# CLK_Distribution.net
KiCad netlist of a schematic drawn in Altium Designer
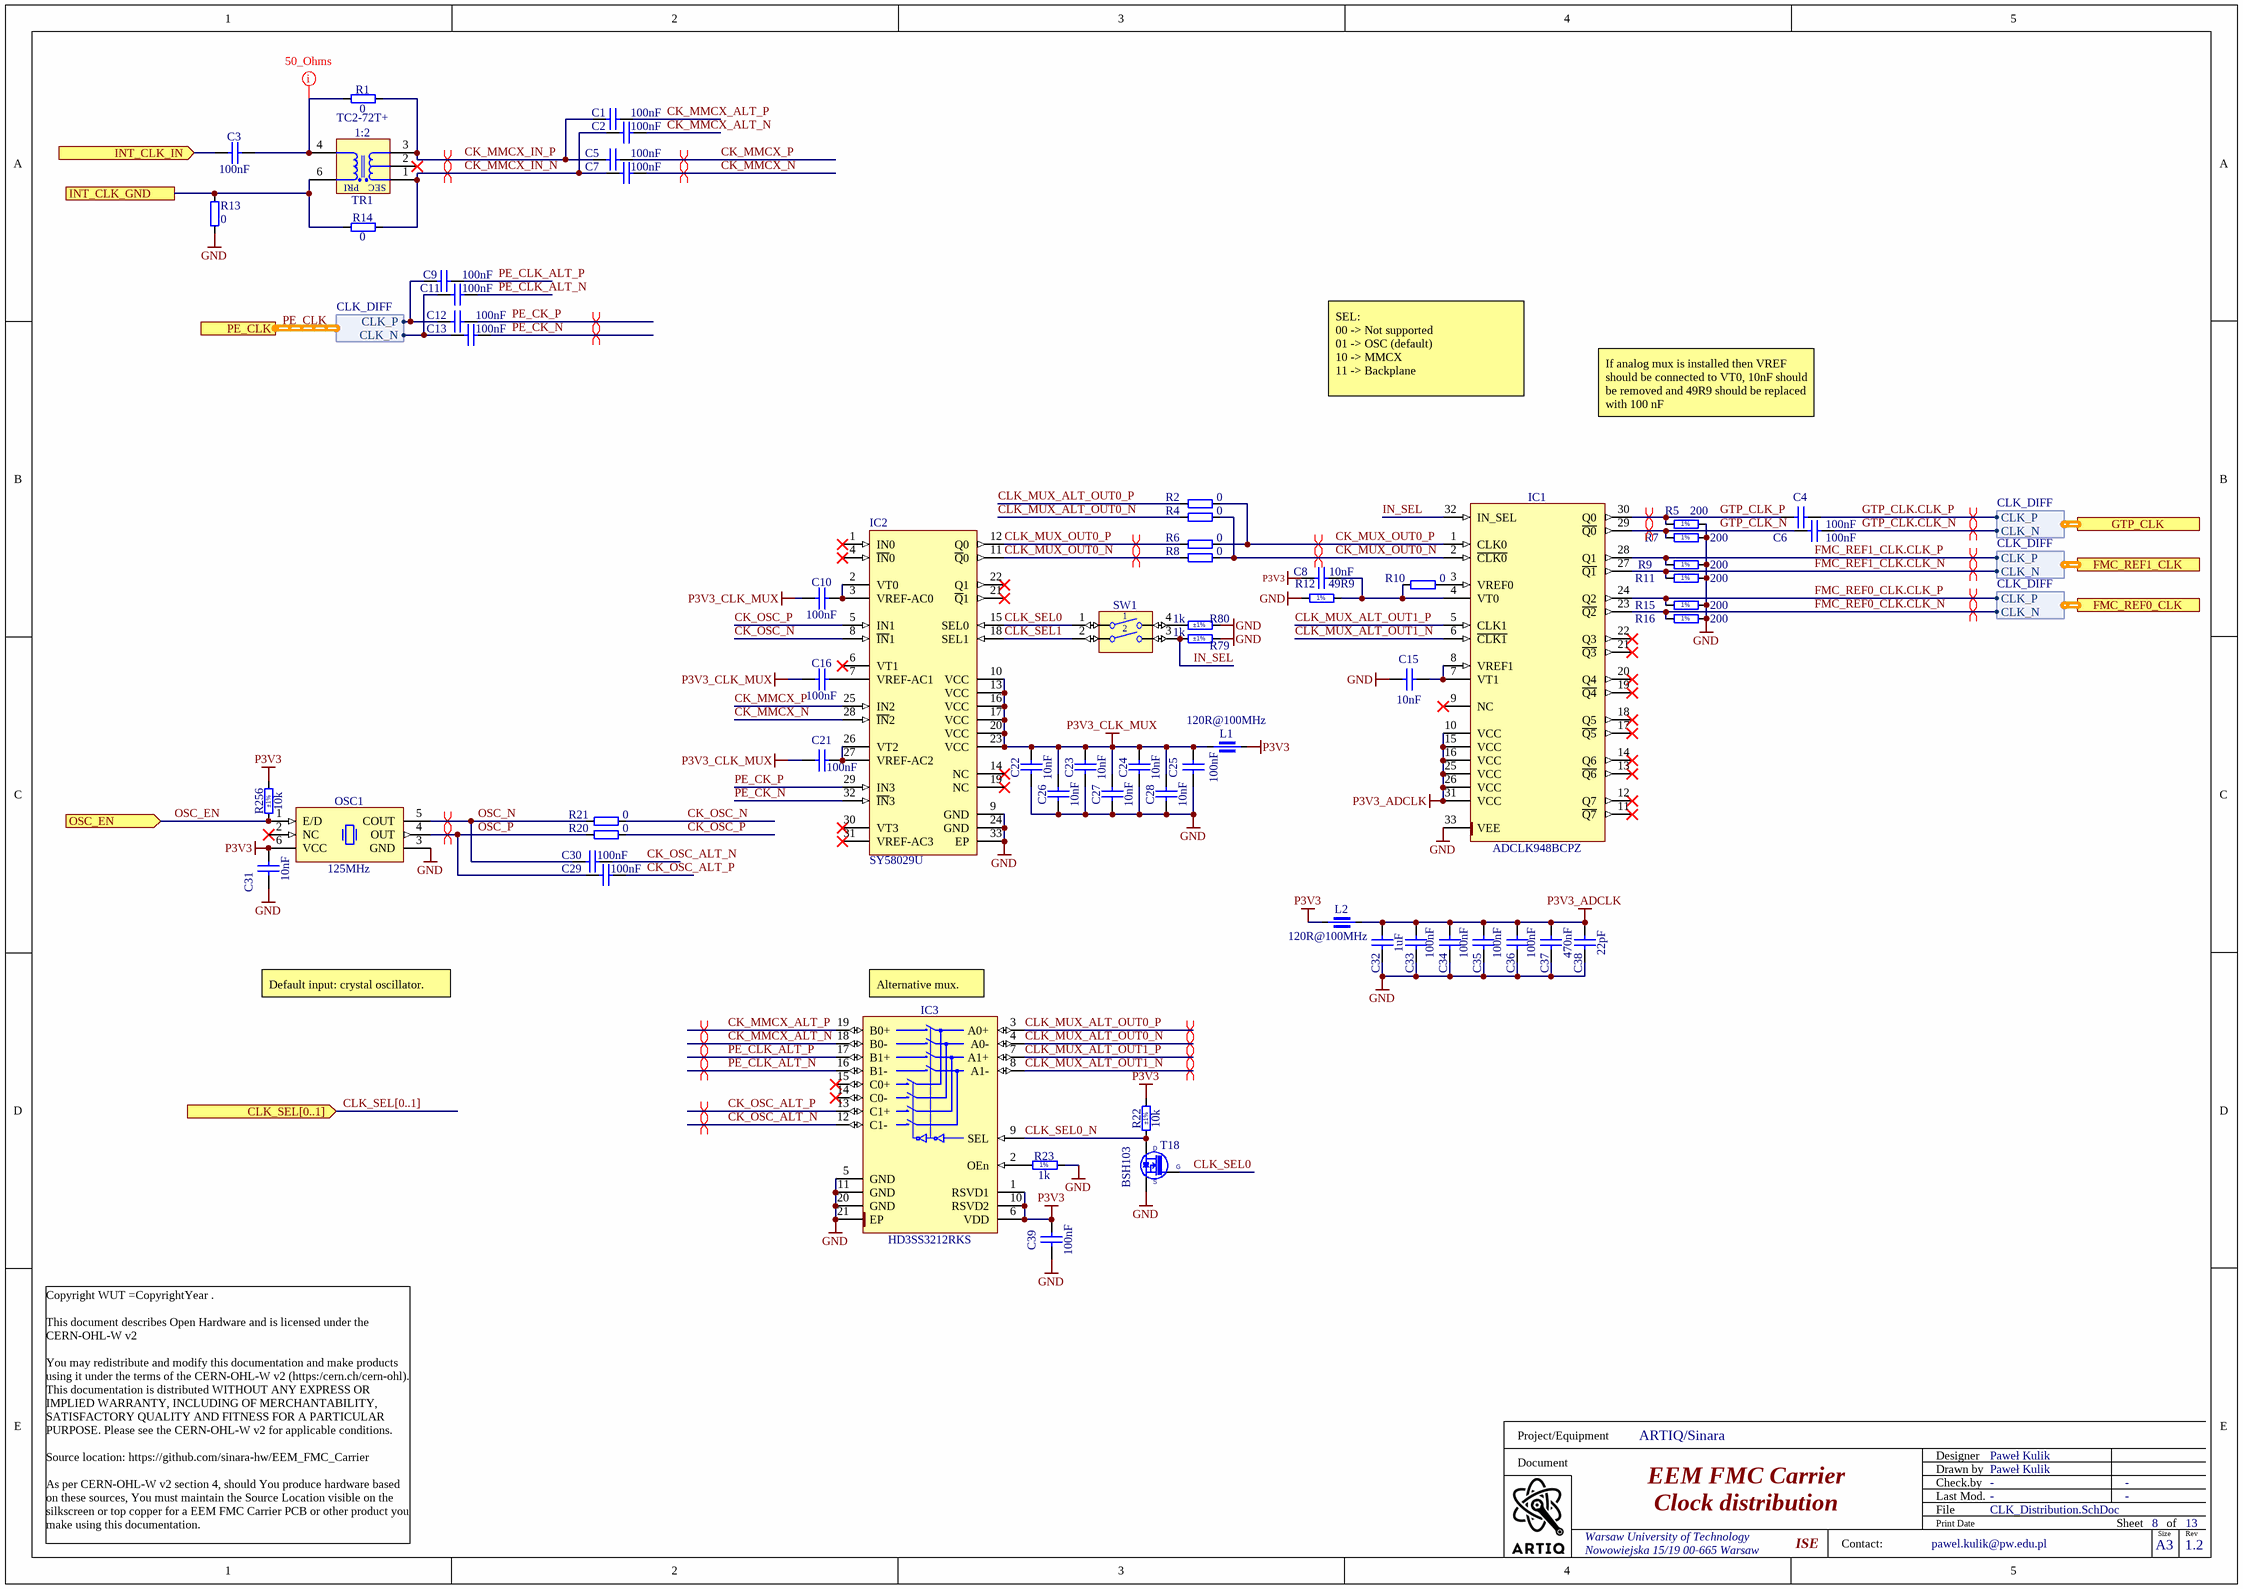
[diagram p0: CLK_Distribution.SchDoc]

(export (version "E")
  (design (tool "Eeschema 10.0.6"))
  (components
    (comp (ref "C1")
      (value "100nF")
      (footprint "CAPC1005X55N")
      (description "Non-polarised capacitor")
      (fields
        (field (name "PART NUMBER") "CC0402_100NF_16V_10%_X5R")
        (field (name "VOLTAGE") "16V")
        (field (name "AUTHOR") "CERN DEM JLC")
      )
      (libsource (lib "Capacitors") (part "Capacitor - non polarized"))
    )
    (comp (ref "C2")
      (value "100nF")
      (footprint "CAPC1005X55N")
      (description "Non-polarised capacitor")
      (fields
        (field (name "PART NUMBER") "CC0402_100NF_16V_10%_X5R")
        (field (name "VOLTAGE") "16V")
        (field (name "AUTHOR") "CERN DEM JLC")
      )
      (libsource (lib "Capacitors") (part "Capacitor - non polarized"))
    )
    (comp (ref "C3")
      (value "100nF")
      (footprint "CAPC1005X55N")
      (description "Non-polarised capacitor")
      (fields
        (field (name "PART NUMBER") "CC0402_100NF_16V_10%_X5R")
        (field (name "VOLTAGE") "16V")
        (field (name "AUTHOR") "CERN DEM JLC")
      )
      (libsource (lib "Capacitors") (part "Capacitor - non polarized"))
    )
    (comp (ref "C4")
      (value "100nF")
      (footprint "CAPC1005X55N")
      (description "Non-polarised capacitor")
      (fields
        (field (name "PART NUMBER") "CC0402_100NF_16V_10%_X5R")
        (field (name "VOLTAGE") "16V")
        (field (name "AUTHOR") "CERN DEM JLC")
      )
      (libsource (lib "Capacitors") (part "Capacitor - non polarized"))
    )
    (comp (ref "C5")
      (value "100nF")
      (footprint "CAPC1005X55N")
      (description "Non-polarised capacitor")
      (fields
        (field (name "PART NUMBER") "CC0402_100NF_16V_10%_X5R")
        (field (name "VOLTAGE") "16V")
        (field (name "AUTHOR") "CERN DEM JLC")
      )
      (libsource (lib "Capacitors") (part "Capacitor - non polarized"))
    )
    (comp (ref "C6")
      (value "100nF")
      (footprint "CAPC1005X55N")
      (description "Non-polarised capacitor")
      (fields
        (field (name "PART NUMBER") "CC0402_100NF_16V_10%_X5R")
        (field (name "VOLTAGE") "16V")
        (field (name "AUTHOR") "CERN DEM JLC")
      )
      (libsource (lib "Capacitors") (part "Capacitor - non polarized"))
    )
    (comp (ref "C7")
      (value "100nF")
      (footprint "CAPC1005X55N")
      (description "Non-polarised capacitor")
      (fields
        (field (name "PART NUMBER") "CC0402_100NF_16V_10%_X5R")
        (field (name "VOLTAGE") "16V")
        (field (name "AUTHOR") "CERN DEM JLC")
      )
      (libsource (lib "Capacitors") (part "Capacitor - non polarized"))
    )
    (comp (ref "C8")
      (value "10nF")
      (footprint "CAPC1005X55N")
      (description "Non-polarised capacitor")
      (fields
        (field (name "PART NUMBER") "CC0402_10NF_16V_10%_X7R")
        (field (name "VOLTAGE") "16V")
        (field (name "AUTHOR") "CERN DEM JLC")
      )
      (libsource (lib "Capacitors") (part "Capacitor - non polarized"))
    )
    (comp (ref "C9")
      (value "100nF")
      (footprint "CAPC1005X55N")
      (description "Non-polarised capacitor")
      (fields
        (field (name "PART NUMBER") "CC0402_100NF_16V_10%_X5R")
        (field (name "VOLTAGE") "16V")
        (field (name "AUTHOR") "CERN DEM JLC")
      )
      (libsource (lib "Capacitors") (part "Capacitor - non polarized"))
    )
    (comp (ref "C10")
      (value "100nF")
      (footprint "CAPC1005X55N")
      (description "Non-polarised capacitor")
      (fields
        (field (name "PART NUMBER") "CC0402_100NF_16V_10%_X5R")
        (field (name "VOLTAGE") "16V")
        (field (name "AUTHOR") "CERN DEM JLC")
      )
      (libsource (lib "Capacitors") (part "Capacitor - non polarized"))
    )
    (comp (ref "C11")
      (value "100nF")
      (footprint "CAPC1005X55N")
      (description "Non-polarised capacitor")
      (fields
        (field (name "PART NUMBER") "CC0402_100NF_16V_10%_X5R")
        (field (name "VOLTAGE") "16V")
        (field (name "AUTHOR") "CERN DEM JLC")
      )
      (libsource (lib "Capacitors") (part "Capacitor - non polarized"))
    )
    (comp (ref "C12")
      (value "100nF")
      (footprint "CAPC1005X55N")
      (description "Non-polarised capacitor")
      (fields
        (field (name "PART NUMBER") "CC0402_100NF_16V_10%_X5R")
        (field (name "VOLTAGE") "16V")
        (field (name "AUTHOR") "CERN DEM JLC")
      )
      (libsource (lib "Capacitors") (part "Capacitor - non polarized"))
    )
    (comp (ref "C13")
      (value "100nF")
      (footprint "CAPC1005X55N")
      (description "Non-polarised capacitor")
      (fields
        (field (name "PART NUMBER") "CC0402_100NF_16V_10%_X5R")
        (field (name "VOLTAGE") "16V")
        (field (name "AUTHOR") "CERN DEM JLC")
      )
      (libsource (lib "Capacitors") (part "Capacitor - non polarized"))
    )
    (comp (ref "C15")
      (value "10nF")
      (footprint "CAPC1005X55N")
      (description "Non-polarised capacitor")
      (fields
        (field (name "PART NUMBER") "CC0402_10NF_16V_10%_X7R")
        (field (name "VOLTAGE") "16V")
        (field (name "AUTHOR") "CERN DEM JLC")
      )
      (libsource (lib "Capacitors") (part "Capacitor - non polarized"))
    )
    (comp (ref "C16")
      (value "100nF")
      (footprint "CAPC1005X55N")
      (description "Non-polarised capacitor")
      (fields
        (field (name "PART NUMBER") "CC0402_100NF_16V_10%_X5R")
        (field (name "VOLTAGE") "16V")
        (field (name "AUTHOR") "CERN DEM JLC")
      )
      (libsource (lib "Capacitors") (part "Capacitor - non polarized"))
    )
    (comp (ref "C21")
      (value "100nF")
      (footprint "CAPC1005X55N")
      (description "Non-polarised capacitor")
      (fields
        (field (name "PART NUMBER") "CC0402_100NF_16V_10%_X5R")
        (field (name "VOLTAGE") "16V")
        (field (name "AUTHOR") "CERN DEM JLC")
      )
      (libsource (lib "Capacitors") (part "Capacitor - non polarized"))
    )
    (comp (ref "C22")
      (value "10nF")
      (footprint "CAPC1005X55N")
      (description "Non-polarised capacitor")
      (fields
        (field (name "PART NUMBER") "CC0402_10NF_16V_10%_X7R")
        (field (name "VOLTAGE") "16V")
        (field (name "AUTHOR") "CERN DEM JLC")
      )
      (libsource (lib "Capacitors") (part "Capacitor - non polarized"))
    )
    (comp (ref "C23")
      (value "10nF")
      (footprint "CAPC1005X55N")
      (description "Non-polarised capacitor")
      (fields
        (field (name "PART NUMBER") "CC0402_10NF_16V_10%_X7R")
        (field (name "VOLTAGE") "16V")
        (field (name "AUTHOR") "CERN DEM JLC")
      )
      (libsource (lib "Capacitors") (part "Capacitor - non polarized"))
    )
    (comp (ref "C24")
      (value "10nF")
      (footprint "CAPC1005X55N")
      (description "Non-polarised capacitor")
      (fields
        (field (name "PART NUMBER") "CC0402_10NF_16V_10%_X7R")
        (field (name "VOLTAGE") "16V")
        (field (name "AUTHOR") "CERN DEM JLC")
      )
      (libsource (lib "Capacitors") (part "Capacitor - non polarized"))
    )
    (comp (ref "C25")
      (value "100nF")
      (footprint "CAPC1005X55N")
      (description "Non-polarised capacitor")
      (fields
        (field (name "PART NUMBER") "CC0402_100NF_16V_10%_X5R")
        (field (name "VOLTAGE") "16V")
        (field (name "AUTHOR") "CERN DEM JLC")
      )
      (libsource (lib "Capacitors") (part "Capacitor - non polarized"))
    )
    (comp (ref "C26")
      (value "10nF")
      (footprint "CAPC1005X55N")
      (description "Non-polarised capacitor")
      (fields
        (field (name "PART NUMBER") "CC0402_10NF_16V_10%_X7R")
        (field (name "VOLTAGE") "16V")
        (field (name "AUTHOR") "CERN DEM JLC")
      )
      (libsource (lib "Capacitors") (part "Capacitor - non polarized"))
    )
    (comp (ref "C27")
      (value "10nF")
      (footprint "CAPC1005X55N")
      (description "Non-polarised capacitor")
      (fields
        (field (name "PART NUMBER") "CC0402_10NF_16V_10%_X7R")
        (field (name "VOLTAGE") "16V")
        (field (name "AUTHOR") "CERN DEM JLC")
      )
      (libsource (lib "Capacitors") (part "Capacitor - non polarized"))
    )
    (comp (ref "C28")
      (value "10nF")
      (footprint "CAPC1005X55N")
      (description "Non-polarised capacitor")
      (fields
        (field (name "PART NUMBER") "CC0402_10NF_16V_10%_X7R")
        (field (name "VOLTAGE") "16V")
        (field (name "AUTHOR") "CERN DEM JLC")
      )
      (libsource (lib "Capacitors") (part "Capacitor - non polarized"))
    )
    (comp (ref "C29")
      (value "100nF")
      (footprint "CAPC1005X55N")
      (description "Non-polarised capacitor")
      (fields
        (field (name "PART NUMBER") "CC0402_100NF_16V_10%_X5R")
        (field (name "VOLTAGE") "16V")
        (field (name "AUTHOR") "CERN DEM JLC")
      )
      (libsource (lib "Capacitors") (part "Capacitor - non polarized"))
    )
    (comp (ref "C30")
      (value "100nF")
      (footprint "CAPC1005X55N")
      (description "Non-polarised capacitor")
      (fields
        (field (name "PART NUMBER") "CC0402_100NF_16V_10%_X5R")
        (field (name "VOLTAGE") "16V")
        (field (name "AUTHOR") "CERN DEM JLC")
      )
      (libsource (lib "Capacitors") (part "Capacitor - non polarized"))
    )
    (comp (ref "C31")
      (value "10nF")
      (footprint "CAPC1005X55N")
      (description "Non-polarised capacitor")
      (fields
        (field (name "PART NUMBER") "CC0402_10NF_16V_10%_X7R")
        (field (name "VOLTAGE") "16V")
        (field (name "AUTHOR") "CERN DEM JLC")
      )
      (libsource (lib "Capacitors") (part "Capacitor - non polarized"))
    )
    (comp (ref "C32")
      (value "1uF")
      (footprint "CAPC1005X55N")
      (description "Non-polarised capacitor")
      (fields
        (field (name "PART NUMBER") "CC0402_1UF_16V_10%_X5R")
        (field (name "VOLTAGE") "16V")
        (field (name "AUTHOR") "CERN DEM JLC")
      )
      (libsource (lib "Capacitors") (part "Capacitor - non polarized"))
    )
    (comp (ref "C33")
      (value "100nF")
      (footprint "CAPC0603X33N")
      (description "Non-polarised capacitor")
      (fields
        (field (name "PART NUMBER") "CC0201_100NF_6.3V_10%_X5R")
        (field (name "VOLTAGE") "6.3V")
        (field (name "AUTHOR") "CERN DEM JLC")
      )
      (libsource (lib "Capacitors") (part "Capacitor - non polarized"))
    )
    (comp (ref "C34")
      (value "100nF")
      (footprint "CAPC0603X33N")
      (description "Non-polarised capacitor")
      (fields
        (field (name "PART NUMBER") "CC0201_100NF_6.3V_10%_X5R")
        (field (name "VOLTAGE") "6.3V")
        (field (name "AUTHOR") "CERN DEM JLC")
      )
      (libsource (lib "Capacitors") (part "Capacitor - non polarized"))
    )
    (comp (ref "C35")
      (value "100nF")
      (footprint "CAPC0603X33N")
      (description "Non-polarised capacitor")
      (fields
        (field (name "PART NUMBER") "CC0201_100NF_6.3V_10%_X5R")
        (field (name "VOLTAGE") "6.3V")
        (field (name "AUTHOR") "CERN DEM JLC")
      )
      (libsource (lib "Capacitors") (part "Capacitor - non polarized"))
    )
    (comp (ref "C36")
      (value "100nF")
      (footprint "CAPC0603X33N")
      (description "Non-polarised capacitor")
      (fields
        (field (name "PART NUMBER") "CC0201_100NF_6.3V_10%_X5R")
        (field (name "VOLTAGE") "6.3V")
        (field (name "AUTHOR") "CERN DEM JLC")
      )
      (libsource (lib "Capacitors") (part "Capacitor - non polarized"))
    )
    (comp (ref "C37")
      (value "470nF")
      (footprint "CAPC0603X33N")
      (description "Non-polarised capacitor")
      (fields
        (field (name "PART NUMBER") "CC0201_470NF_4V_20%_X5R")
        (field (name "VOLTAGE") "4V")
        (field (name "AUTHOR") "CERN DEM JLC")
      )
      (libsource (lib "Capacitors") (part "Capacitor - non polarized"))
    )
    (comp (ref "C38")
      (value "22pF")
      (footprint "CAPC1005X55N")
      (description "Non-polarised capacitor")
      (fields
        (field (name "PART NUMBER") "CC0402_22PF_50V_5%_C0G")
        (field (name "VOLTAGE") "50V")
        (field (name "AUTHOR") "CERN DEM JLC")
      )
      (libsource (lib "Capacitors") (part "Capacitor - non polarized"))
    )
    (comp (ref "C39")
      (value "100nF")
      (footprint "CAPC1005X55N")
      (description "Non-polarised capacitor")
      (fields
        (field (name "PART NUMBER") "CC0402_100NF_25V_10%_X7R_YUDEN_TMK105B7104KVHF")
        (field (name "VOLTAGE") "25V")
        (field (name "AUTHOR") "CERN DEM JLC")
      )
      (libsource (lib "Capacitors") (part "Capacitor - non polarized"))
    )
    (comp (ref "IC1")
      (value "ADCLK948BCPZ")
      (footprint "QFN50P500X500X80-33N-S285")
      (description "Two Selectable Inputs, 8 LVPECL Outputs, SiGe Clock Fanout Buffer")
      (fields (field (name "MANUFACTURER") "ANALOG DEVICES") (field (name "AUTHOR") "CERN DEM MR"))
      (libsource (lib "ICs And Semiconductors") (part "ADCLK948"))
    )
    (comp (ref "IC2")
      (value "SY58029U")
      (footprint "MLF-32")
      (description "ULTRA PRECISION DIFFERENTIAL LVPECL 4:1 MUX with 1:2 FANOUT and INTERNAL TERMINATION")
      (fields (field (name "MANUFACTURER") "Microchip"))
      (libsource (lib "Schlib1") (part "SY58029U"))
    )
    (comp (ref "IC3")
      (value "HD3SS3212RKS")
      (footprint "TEXAS_RKS0020A")
      (description "Two-Channel Differential 2:1/1:2 USB3.1 Mux/Demux")
      (fields (field (name "MANUFACTURER") "TEXAS INSTRUMENTS") (field (name "AUTHOR") "CERN DEM BC"))
      (libsource (lib "ICs And Semiconductors") (part "HD3SS3212RKS"))
    )
    (comp (ref "L1")
      (value "120R@100MHz")
      (footprint "INDC1608X65N")
      (fields
        (field (name "PART NUMBER") "IND0603_MURATA_BLM18SG121TN1D")
        (field (name "POWER") "3A")
        (field (name "MANUFACTURER") "MURATA")
        (field (name "AUTHOR") "CERN DEM JLC")
      )
      (libsource (lib "Inductors & Transformers") (part "Ferrite Bead"))
    )
    (comp (ref "L2")
      (value "120R@100MHz")
      (footprint "INDC1608X65N")
      (fields
        (field (name "PART NUMBER") "IND0603_MURATA_BLM18SG121TN1D")
        (field (name "POWER") "3A")
        (field (name "MANUFACTURER") "MURATA")
        (field (name "AUTHOR") "CERN DEM JLC")
      )
      (libsource (lib "Inductors & Transformers") (part "Ferrite Bead"))
    )
    (comp (ref "OSC1")
      (value "125MHz")
      (footprint "OSC_CRYSTEK_CCLD-033")
      (description "3.3V, ± 50ppm, 0°C to +70°C, Surface Mount LVDS Clock Oscillator (CCLD-033 Series)")
      (fields
        (field (name "PART NUMBER") "OSC_125MHZ_CRYSTEK_CCLD-033-50-125.000")
        (field (name "MANUFACTURER") "CRYSTEK CRYSTAL")
        (field (name "AUTHOR") "CERN DEM JLC")
      )
      (libsource (lib "Schlib1") (part "OSC_CRYSTEK_CCLD-033"))
    )
    (comp (ref "R1")
      (value "0")
      (footprint "RESC1005X40N")
      (description "Resistor")
      (fields
        (field (name "PART NUMBER") "R0402_0R_JUMPER")
        (field (name "MANUFACTURER") "GENERIC")
        (field (name "AUTHOR") "CERN DEM JLC")
      )
      (libsource (lib "Resistors") (part "Resistor"))
    )
    (comp (ref "R2")
      (value "0")
      (footprint "RESC0603X28N")
      (description "Resistor")
      (fields
        (field (name "PART NUMBER") "R0201_0R_JUMPER")
        (field (name "MANUFACTURER") "GENERIC")
        (field (name "AUTHOR") "CERN DEM JLC")
      )
      (libsource (lib "Resistors") (part "Resistor"))
    )
    (comp (ref "R4")
      (value "0")
      (footprint "RESC0603X28N")
      (description "Resistor")
      (fields
        (field (name "PART NUMBER") "R0201_0R_JUMPER")
        (field (name "MANUFACTURER") "GENERIC")
        (field (name "AUTHOR") "CERN DEM JLC")
      )
      (libsource (lib "Resistors") (part "Resistor"))
    )
    (comp (ref "R5")
      (value "200")
      (footprint "RESC1005X40N")
      (description "Resistor - 1%")
      (fields
        (field (name "PART NUMBER") "R0402_200R_1%_0.0625W_100PPM")
        (field (name "POWER") "0.0625W")
        (field (name "AUTHOR") "CERN DEM JLC")
      )
      (libsource (lib "Resistors") (part "Resistor - 1%"))
    )
    (comp (ref "R6")
      (value "0")
      (footprint "RESC0603X28N")
      (description "Resistor")
      (fields
        (field (name "PART NUMBER") "R0201_0R_JUMPER")
        (field (name "MANUFACTURER") "GENERIC")
        (field (name "AUTHOR") "CERN DEM JLC")
      )
      (libsource (lib "Resistors") (part "Resistor"))
    )
    (comp (ref "R7")
      (value "200")
      (footprint "RESC1005X40N")
      (description "Resistor - 1%")
      (fields
        (field (name "PART NUMBER") "R0402_200R_1%_0.0625W_100PPM")
        (field (name "POWER") "0.0625W")
        (field (name "AUTHOR") "CERN DEM JLC")
      )
      (libsource (lib "Resistors") (part "Resistor - 1%"))
    )
    (comp (ref "R8")
      (value "0")
      (footprint "RESC0603X28N")
      (description "Resistor")
      (fields
        (field (name "PART NUMBER") "R0201_0R_JUMPER")
        (field (name "MANUFACTURER") "GENERIC")
        (field (name "AUTHOR") "CERN DEM JLC")
      )
      (libsource (lib "Resistors") (part "Resistor"))
    )
    (comp (ref "R9")
      (value "200")
      (footprint "RESC1005X40N")
      (description "Resistor - 1%")
      (fields
        (field (name "PART NUMBER") "R0402_200R_1%_0.0625W_100PPM")
        (field (name "POWER") "0.0625W")
        (field (name "AUTHOR") "CERN DEM JLC")
      )
      (libsource (lib "Resistors") (part "Resistor - 1%"))
    )
    (comp (ref "R10")
      (value "0")
      (footprint "RESC0603X28N")
      (description "Resistor")
      (fields
        (field (name "PART NUMBER") "R0201_0R_JUMPER")
        (field (name "MANUFACTURER") "GENERIC")
        (field (name "AUTHOR") "CERN DEM JLC")
      )
      (libsource (lib "Resistors") (part "Resistor"))
    )
    (comp (ref "R11")
      (value "200")
      (footprint "RESC1005X40N")
      (description "Resistor - 1%")
      (fields
        (field (name "PART NUMBER") "R0402_200R_1%_0.0625W_100PPM")
        (field (name "POWER") "0.0625W")
        (field (name "AUTHOR") "CERN DEM JLC")
      )
      (libsource (lib "Resistors") (part "Resistor - 1%"))
    )
    (comp (ref "R12")
      (value "49R9")
      (footprint "RESC1005X40N")
      (description "Resistor - 1%")
      (fields
        (field (name "PART NUMBER") "R0402_49R9_1%_0.0625W_100PPM")
        (field (name "POWER") "0.0625W")
        (field (name "AUTHOR") "CERN DEM JLC")
      )
      (libsource (lib "Resistors") (part "Resistor - 1%"))
    )
    (comp (ref "R13")
      (value "0")
      (footprint "RESC1005X40N")
      (description "Resistor")
      (fields
        (field (name "PART NUMBER") "R0402_0R_JUMPER")
        (field (name "MANUFACTURER") "GENERIC")
        (field (name "AUTHOR") "CERN DEM JLC")
      )
      (libsource (lib "Resistors") (part "Resistor"))
    )
    (comp (ref "R14")
      (value "0")
      (footprint "RESC1005X40N")
      (description "Resistor")
      (fields
        (field (name "PART NUMBER") "R0402_0R_JUMPER")
        (field (name "MANUFACTURER") "GENERIC")
        (field (name "AUTHOR") "CERN DEM JLC")
      )
      (libsource (lib "Resistors") (part "Resistor"))
    )
    (comp (ref "R15")
      (value "200")
      (footprint "RESC1005X40N")
      (description "Resistor - 1%")
      (fields
        (field (name "PART NUMBER") "R0402_200R_1%_0.0625W_100PPM")
        (field (name "POWER") "0.0625W")
        (field (name "AUTHOR") "CERN DEM JLC")
      )
      (libsource (lib "Resistors") (part "Resistor - 1%"))
    )
    (comp (ref "R16")
      (value "200")
      (footprint "RESC1005X40N")
      (description "Resistor - 1%")
      (fields
        (field (name "PART NUMBER") "R0402_200R_1%_0.0625W_100PPM")
        (field (name "POWER") "0.0625W")
        (field (name "AUTHOR") "CERN DEM JLC")
      )
      (libsource (lib "Resistors") (part "Resistor - 1%"))
    )
    (comp (ref "R20")
      (value "0")
      (footprint "RESC1005X40N")
      (description "Resistor")
      (fields
        (field (name "PART NUMBER") "R0402_0R_JUMPER")
        (field (name "MANUFACTURER") "GENERIC")
        (field (name "AUTHOR") "CERN DEM JLC")
      )
      (libsource (lib "Resistors") (part "Resistor"))
    )
    (comp (ref "R21")
      (value "0")
      (footprint "RESC1005X40N")
      (description "Resistor")
      (fields
        (field (name "PART NUMBER") "R0402_0R_JUMPER")
        (field (name "MANUFACTURER") "GENERIC")
        (field (name "AUTHOR") "CERN DEM JLC")
      )
      (libsource (lib "Resistors") (part "Resistor"))
    )
    (comp (ref "R22")
      (value "10k")
      (footprint "RESC1005X40N")
      (description "Resistor - 1%")
      (fields
        (field (name "TOLERANCE") "±1%")
        (field (name "PART NUMBER") "R0402_10K_1%_0.0625W_100PPM")
        (field (name "POWER") "0.0625W")
        (field (name "AUTHOR") "CERN DEM JLC")
      )
      (libsource (lib "Resistors") (part "Resistor - 1%"))
    )
    (comp (ref "R23")
      (value "1k")
      (footprint "RESC1005X40N")
      (description "Resistor - 1%")
      (fields
        (field (name "PART NUMBER") "R0402_1K_1%_0.0625W_100PPM")
        (field (name "POWER") "0.0625W")
        (field (name "AUTHOR") "CERN DEM JLC")
      )
      (libsource (lib "Resistors") (part "Resistor - 1%"))
    )
    (comp (ref "R79")
      (value "1k")
      (footprint "RESC1005X40N")
      (description "Resistor - 1%")
      (fields
        (field (name "TOLERANCE") "±1%")
        (field (name "PART NUMBER") "R0402_1K_1%_0.0625W_100PPM")
        (field (name "POWER") "0.0625W")
        (field (name "AUTHOR") "CERN DEM JLC")
      )
      (libsource (lib "Resistors") (part "Resistor - 1%"))
    )
    (comp (ref "R80")
      (value "1k")
      (footprint "RESC1005X40N")
      (description "Resistor - 1%")
      (fields
        (field (name "TOLERANCE") "±1%")
        (field (name "PART NUMBER") "R0402_1K_1%_0.0625W_100PPM")
        (field (name "POWER") "0.0625W")
        (field (name "AUTHOR") "CERN DEM JLC")
      )
      (libsource (lib "Resistors") (part "Resistor - 1%"))
    )
    (comp (ref "R256")
      (value "10k")
      (footprint "RESC1005X40N")
      (description "Resistor - 1%")
      (fields
        (field (name "TOLERANCE") "±1%")
        (field (name "PART NUMBER") "R0402_10K_1%_0.0625W_100PPM")
        (field (name "POWER") "0.0625W")
        (field (name "AUTHOR") "CERN DEM JLC")
      )
      (libsource (lib "Resistors") (part "Resistor - 1%"))
    )
    (comp (ref "SW1")
      (value "Switch")
      (footprint "SW_TYCO_1571983-1")
      (description "2 Ways SPST DIP Switch")
      (fields
        (field (name "PART NUMBER") "SW_TYCO_1571983-1")
        (field (name "MANUFACTURER") "TYCO")
        (field (name "AUTHOR") "CERN DEM JLC")
      )
      (libsource (lib "Eletro-mechanical") (part "SW 2x SPST DIP Switch"))
    )
    (comp (ref "T18")
      (value "BSH103")
      (footprint "SOT95P230X110-3N")
      (description "N-CHANNEL MOSFET WITH DIODE")
      (fields (field (name "MANUFACTURER") "NEXPERIA") (field (name "AUTHOR") "CERN DEM JLC"))
      (libsource (lib "ICs And Semiconductors") (part "N-MOSFET-D 1G 2S 3D"))
    )
    (comp (ref "TR1")
      (value "1:2")
      (footprint "XFMR_MINI-CIRCUITS_AT1521")
      (description "50 Ohms 10 to 700 MHzz RF Transformer")
      (fields
        (field (name "MANUFACTURER") "MINI-CIRCUITS")
        (field (name "MANUFACTURER PART NUMBER") "TC2-72T+")
        (field (name "PART NUMBER") "XFMR_MINI-CIRCUITS_TC2-72T+")
        (field (name "AUTHOR") "GK")
      )
      (libsource (lib "Inductors_Transformers") (part "XFMR_MINI-CIRCUITS_TC2-72T+"))
    )
  )
  (nets
    (net (code "3") (name "/CK_MMCX_ALT_N") (class "Default")
      (node (ref "C2") (pin "2") (pinfunction "2_2") (pintype "passive"))
      (node (ref "IC3") (pin "18") (pinfunction "B0-_18") (pintype "bidirectional"))
    )
    (net (code "4") (name "/CK_MMCX_ALT_P") (class "Default")
      (node (ref "C1") (pin "2") (pinfunction "2_2") (pintype "passive"))
      (node (ref "IC3") (pin "19") (pinfunction "B0+_19") (pintype "bidirectional"))
    )
    (net (code "5") (name "/CK_MMCX_IN_N") (class "Default")
      (node (ref "C2") (pin "1") (pinfunction "1_1") (pintype "passive"))
      (node (ref "C7") (pin "1") (pinfunction "1_1") (pintype "passive"))
      (node (ref "R14") (pin "2") (pinfunction "2_2") (pintype "passive"))
      (node (ref "TR1") (pin "1") (pinfunction "SDOT_1") (pintype "passive"))
    )
    (net (code "6") (name "/CK_MMCX_IN_P") (class "Default")
      (node (ref "C1") (pin "1") (pinfunction "1_1") (pintype "passive"))
      (node (ref "C5") (pin "1") (pinfunction "1_1") (pintype "passive"))
      (node (ref "R1") (pin "2") (pinfunction "2_2") (pintype "passive"))
      (node (ref "TR1") (pin "3") (pinfunction "S_3") (pintype "passive"))
    )
    (net (code "7") (name "/CK_MMCX_N") (class "Default")
      (node (ref "C7") (pin "2") (pinfunction "2_2") (pintype "passive"))
      (node (ref "IC2") (pin "28") (pinfunction "~{IN}2_28") (pintype "input"))
    )
    (net (code "8") (name "/CK_MMCX_P") (class "Default")
      (node (ref "C5") (pin "2") (pinfunction "2_2") (pintype "passive"))
      (node (ref "IC2") (pin "25") (pinfunction "IN2_25") (pintype "input"))
    )
    (net (code "9") (name "/CK_MUX_OUT0_N") (class "Default")
      (node (ref "IC1") (pin "2") (pinfunction "~{CLK0}_2") (pintype "input"))
      (node (ref "R4") (pin "2") (pinfunction "2_2") (pintype "passive"))
      (node (ref "R8") (pin "2") (pinfunction "2_2") (pintype "passive"))
    )
    (net (code "10") (name "/CK_MUX_OUT0_P") (class "Default")
      (node (ref "IC1") (pin "1") (pinfunction "CLK0_1") (pintype "input"))
      (node (ref "R2") (pin "2") (pinfunction "2_2") (pintype "passive"))
      (node (ref "R6") (pin "2") (pinfunction "2_2") (pintype "passive"))
    )
    (net (code "11") (name "/CK_OSC_ALT_N") (class "Default")
      (node (ref "C30") (pin "2") (pinfunction "2_2") (pintype "passive"))
      (node (ref "IC3") (pin "12") (pinfunction "C1-_12") (pintype "bidirectional"))
    )
    (net (code "12") (name "/CK_OSC_ALT_P") (class "Default")
      (node (ref "C29") (pin "2") (pinfunction "2_2") (pintype "passive"))
      (node (ref "IC3") (pin "13") (pinfunction "C1+_13") (pintype "bidirectional"))
    )
    (net (code "13") (name "/CK_OSC_N") (class "Default")
      (node (ref "IC2") (pin "8") (pinfunction "~{IN}1_8") (pintype "input"))
      (node (ref "R21") (pin "2") (pinfunction "2_2") (pintype "passive"))
    )
    (net (code "14") (name "/CK_OSC_P") (class "Default")
      (node (ref "IC2") (pin "5") (pinfunction "IN1_5") (pintype "input"))
      (node (ref "R20") (pin "2") (pinfunction "2_2") (pintype "passive"))
    )
    (net (code "15") (name "/CLK_MUX_ALT_OUT0_N") (class "Default")
      (node (ref "IC3") (pin "4") (pinfunction "A0-_4") (pintype "bidirectional"))
      (node (ref "R4") (pin "1") (pinfunction "1_1") (pintype "passive"))
    )
    (net (code "16") (name "/CLK_MUX_ALT_OUT0_P") (class "Default")
      (node (ref "IC3") (pin "3") (pinfunction "A0+_3") (pintype "bidirectional"))
      (node (ref "R2") (pin "1") (pinfunction "1_1") (pintype "passive"))
    )
    (net (code "17") (name "/CLK_MUX_ALT_OUT1_N") (class "Default")
      (node (ref "IC1") (pin "6") (pinfunction "~{CLK1}_6") (pintype "input"))
      (node (ref "IC3") (pin "8") (pinfunction "A1-_8") (pintype "bidirectional"))
    )
    (net (code "18") (name "/CLK_MUX_ALT_OUT1_P") (class "Default")
      (node (ref "IC1") (pin "5") (pinfunction "CLK1_5") (pintype "input"))
      (node (ref "IC3") (pin "7") (pinfunction "A1+_7") (pintype "bidirectional"))
    )
    (net (code "19") (name "/CLK_MUX_OUT0_N") (class "Default")
      (node (ref "IC2") (pin "11") (pinfunction "~{Q}0_11") (pintype "output"))
      (node (ref "R8") (pin "1") (pinfunction "1_1") (pintype "passive"))
    )
    (net (code "20") (name "/CLK_MUX_OUT0_P") (class "Default")
      (node (ref "IC2") (pin "12") (pinfunction "Q0_12") (pintype "output"))
      (node (ref "R6") (pin "1") (pinfunction "1_1") (pintype "passive"))
    )
    (net (code "21") (name "/CLK_SEL0") (class "Default")
      (node (ref "IC2") (pin "15") (pinfunction "SEL0_15") (pintype "input"))
      (node (ref "SW1") (pin "1") (pinfunction "1_1") (pintype "bidirectional"))
      (node (ref "T18") (pin "1") (pinfunction "G_1") (pintype "passive"))
    )
    (net (code "22") (name "/CLK_SEL0_N") (class "Default")
      (node (ref "IC3") (pin "9") (pinfunction "SEL_9") (pintype "input"))
      (node (ref "R22") (pin "1") (pinfunction "1_1") (pintype "passive"))
      (node (ref "T18") (pin "3") (pinfunction "D_3") (pintype "passive"))
    )
    (net (code "23") (name "/CLK_SEL1") (class "Default")
      (node (ref "IC2") (pin "18") (pinfunction "SEL1_18") (pintype "input"))
      (node (ref "SW1") (pin "2") (pinfunction "2_2") (pintype "bidirectional"))
    )
    (net (code "25") (name "/FMC_REF0_CLK.CLK_N") (class "Default")
      (node (ref "IC1") (pin "23") (pinfunction "~{Q2}_23") (pintype "output"))
      (node (ref "R16") (pin "1") (pinfunction "1_1") (pintype "passive"))
    )
    (net (code "26") (name "/FMC_REF0_CLK.CLK_P") (class "Default")
      (node (ref "IC1") (pin "24") (pinfunction "Q2_24") (pintype "output"))
      (node (ref "R15") (pin "1") (pinfunction "1_1") (pintype "passive"))
    )
    (net (code "27") (name "/FMC_REF1_CLK.CLK_N") (class "Default")
      (node (ref "IC1") (pin "27") (pinfunction "~{Q1}_27") (pintype "output"))
      (node (ref "R11") (pin "1") (pinfunction "1_1") (pintype "passive"))
    )
    (net (code "28") (name "/FMC_REF1_CLK.CLK_P") (class "Default")
      (node (ref "IC1") (pin "28") (pinfunction "Q1_28") (pintype "output"))
      (node (ref "R9") (pin "1") (pinfunction "1_1") (pintype "passive"))
    )
    (net (code "29") (name "/GTP_CLK.CLK_N") (class "Default")
      (node (ref "C6") (pin "2") (pinfunction "2_2") (pintype "passive"))
    )
    (net (code "30") (name "/GTP_CLK.CLK_P") (class "Default")
      (node (ref "C4") (pin "2") (pinfunction "2_2") (pintype "passive"))
    )
    (net (code "31") (name "/GTP_CLK_N") (class "Default")
      (node (ref "C6") (pin "1") (pinfunction "1_1") (pintype "passive"))
      (node (ref "IC1") (pin "29") (pinfunction "~{Q0}_29") (pintype "output"))
      (node (ref "R7") (pin "1") (pinfunction "1_1") (pintype "passive"))
    )
    (net (code "32") (name "/GTP_CLK_P") (class "Default")
      (node (ref "C4") (pin "1") (pinfunction "1_1") (pintype "passive"))
      (node (ref "IC1") (pin "30") (pinfunction "Q0_30") (pintype "output"))
      (node (ref "R5") (pin "1") (pinfunction "1_1") (pintype "passive"))
    )
    (net (code "33") (name "/INT_CLK_GND") (class "Default")
      (node (ref "R13") (pin "2") (pinfunction "2_2") (pintype "passive"))
      (node (ref "R14") (pin "1") (pinfunction "1_1") (pintype "passive"))
      (node (ref "TR1") (pin "6") (pinfunction "PDOT_6") (pintype "passive"))
    )
    (net (code "34") (name "/INT_CLK_IN") (class "Default")
      (node (ref "C3") (pin "1") (pinfunction "1_1") (pintype "passive"))
    )
    (net (code "35") (name "/IN_SEL") (class "Default")
      (node (ref "IC1") (pin "32") (pinfunction "IN_SEL_32") (pintype "input"))
      (node (ref "R79") (pin "1") (pinfunction "1_1") (pintype "passive"))
      (node (ref "SW1") (pin "3") (pinfunction "3_3") (pintype "bidirectional"))
    )
    (net (code "36") (name "/OSC_EN") (class "Default")
      (node (ref "OSC1") (pin "1") (pinfunction "E/D_1") (pintype "input"))
      (node (ref "R256") (pin "1") (pinfunction "1_1") (pintype "passive"))
    )
    (net (code "37") (name "/OSC_N") (class "Default")
      (node (ref "C30") (pin "1") (pinfunction "1_1") (pintype "passive"))
      (node (ref "OSC1") (pin "5") (pinfunction "COUT_5") (pintype "passive"))
      (node (ref "R21") (pin "1") (pinfunction "1_1") (pintype "passive"))
    )
    (net (code "38") (name "/OSC_P") (class "Default")
      (node (ref "C29") (pin "1") (pinfunction "1_1") (pintype "passive"))
      (node (ref "OSC1") (pin "4") (pinfunction "OUT_4") (pintype "output"))
      (node (ref "R20") (pin "1") (pinfunction "1_1") (pintype "passive"))
    )
    (net (code "39") (name "/PE_CK_N") (class "Default")
      (node (ref "C13") (pin "2") (pinfunction "2_2") (pintype "passive"))
      (node (ref "IC2") (pin "32") (pinfunction "~{IN}3_32") (pintype "input"))
    )
    (net (code "40") (name "/PE_CK_P") (class "Default")
      (node (ref "C12") (pin "2") (pinfunction "2_2") (pintype "passive"))
      (node (ref "IC2") (pin "29") (pinfunction "IN3_29") (pintype "input"))
    )
    (net (code "41") (name "/PE_CLK_ALT_N") (class "Default")
      (node (ref "C11") (pin "2") (pinfunction "2_2") (pintype "passive"))
      (node (ref "IC3") (pin "16") (pinfunction "B1-_16") (pintype "bidirectional"))
    )
    (net (code "42") (name "/PE_CLK_ALT_P") (class "Default")
      (node (ref "C9") (pin "2") (pinfunction "2_2") (pintype "passive"))
      (node (ref "IC3") (pin "17") (pinfunction "B1+_17") (pintype "bidirectional"))
    )
    (net (code "45") (name "GND") (class "Default")
      (node (ref "C15") (pin "1") (pinfunction "1_1") (pintype "passive"))
      (node (ref "C22") (pin "1") (pinfunction "1_1") (pintype "passive"))
      (node (ref "C23") (pin "1") (pinfunction "1_1") (pintype "passive"))
      (node (ref "C24") (pin "1") (pinfunction "1_1") (pintype "passive"))
      (node (ref "C25") (pin "1") (pinfunction "1_1") (pintype "passive"))
      (node (ref "C26") (pin "1") (pinfunction "1_1") (pintype "passive"))
      (node (ref "C27") (pin "1") (pinfunction "1_1") (pintype "passive"))
      (node (ref "C28") (pin "1") (pinfunction "1_1") (pintype "passive"))
      (node (ref "C31") (pin "1") (pinfunction "1_1") (pintype "passive"))
      (node (ref "C32") (pin "1") (pinfunction "1_1") (pintype "passive"))
      (node (ref "C33") (pin "1") (pinfunction "1_1") (pintype "passive"))
      (node (ref "C34") (pin "1") (pinfunction "1_1") (pintype "passive"))
      (node (ref "C35") (pin "1") (pinfunction "1_1") (pintype "passive"))
      (node (ref "C36") (pin "1") (pinfunction "1_1") (pintype "passive"))
      (node (ref "C37") (pin "1") (pinfunction "1_1") (pintype "passive"))
      (node (ref "C38") (pin "1") (pinfunction "1_1") (pintype "passive"))
      (node (ref "C39") (pin "1") (pinfunction "1_1") (pintype "passive"))
      (node (ref "IC1") (pin "33") (pinfunction "VEE_33") (pintype "power_in"))
      (node (ref "IC2") (pin "24") (pinfunction "GND_24") (pintype "passive"))
      (node (ref "IC2") (pin "33") (pinfunction "EP_33") (pintype "passive"))
      (node (ref "IC2") (pin "9") (pinfunction "GND_9") (pintype "passive"))
      (node (ref "IC3") (pin "11") (pinfunction "GND_11") (pintype "power_in"))
      (node (ref "IC3") (pin "20") (pinfunction "GND_20") (pintype "power_in"))
      (node (ref "IC3") (pin "21") (pinfunction "EP_21") (pintype "power_in"))
      (node (ref "IC3") (pin "5") (pinfunction "GND_5") (pintype "power_in"))
      (node (ref "OSC1") (pin "3") (pinfunction "GND_3") (pintype "power_in"))
      (node (ref "R11") (pin "2") (pinfunction "2_2") (pintype "passive"))
      (node (ref "R12") (pin "1") (pinfunction "1_1") (pintype "passive"))
      (node (ref "R13") (pin "1") (pinfunction "1_1") (pintype "passive"))
      (node (ref "R15") (pin "2") (pinfunction "2_2") (pintype "passive"))
      (node (ref "R16") (pin "2") (pinfunction "2_2") (pintype "passive"))
      (node (ref "R23") (pin "2") (pinfunction "2_2") (pintype "passive"))
      (node (ref "R5") (pin "2") (pinfunction "2_2") (pintype "passive"))
      (node (ref "R7") (pin "2") (pinfunction "2_2") (pintype "passive"))
      (node (ref "R79") (pin "2") (pinfunction "2_2") (pintype "passive"))
      (node (ref "R80") (pin "2") (pinfunction "2_2") (pintype "passive"))
      (node (ref "R9") (pin "2") (pinfunction "2_2") (pintype "passive"))
      (node (ref "T18") (pin "2") (pinfunction "S_2") (pintype "passive"))
    )
    (net (code "46") (name "Net-(C11-Pad1)") (class "Default")
      (node (ref "C11") (pin "1") (pinfunction "1_1") (pintype "passive"))
      (node (ref "C13") (pin "1") (pinfunction "1_1") (pintype "passive"))
    )
    (net (code "47") (name "Net-(C12-Pad1)") (class "Default")
      (node (ref "C12") (pin "1") (pinfunction "1_1") (pintype "passive"))
      (node (ref "C9") (pin "1") (pinfunction "1_1") (pintype "passive"))
    )
    (net (code "48") (name "Net-(IC1-VREF0)") (class "Default")
      (node (ref "IC1") (pin "3") (pinfunction "VREF0_3") (pintype "input"))
      (node (ref "R10") (pin "2") (pinfunction "2_2") (pintype "passive"))
    )
    (net (code "49") (name "Net-(IC1-VREF1)") (class "Default")
      (node (ref "C15") (pin "2") (pinfunction "2_2") (pintype "passive"))
      (node (ref "IC1") (pin "7") (pinfunction "VT1_7") (pintype "passive"))
      (node (ref "IC1") (pin "8") (pinfunction "VREF1_8") (pintype "input"))
    )
    (net (code "50") (name "Net-(IC1-VT0)") (class "Default")
      (node (ref "C8") (pin "2") (pinfunction "2_2") (pintype "passive"))
      (node (ref "IC1") (pin "4") (pinfunction "VT0_4") (pintype "passive"))
      (node (ref "R10") (pin "1") (pinfunction "1_1") (pintype "passive"))
      (node (ref "R12") (pin "2") (pinfunction "2_2") (pintype "passive"))
    )
    (net (code "51") (name "Net-(IC2-VREF-AC0)") (class "Default")
      (node (ref "C10") (pin "2") (pinfunction "2_2") (pintype "passive"))
      (node (ref "IC2") (pin "2") (pinfunction "VT0_2") (pintype "power_in"))
      (node (ref "IC2") (pin "3") (pinfunction "VREF-AC0_3") (pintype "power_in"))
    )
    (net (code "52") (name "Net-(IC2-VREF-AC1)") (class "Default")
      (node (ref "C16") (pin "2") (pinfunction "2_2") (pintype "passive"))
      (node (ref "IC2") (pin "7") (pinfunction "VREF-AC1_7") (pintype "power_in"))
    )
    (net (code "53") (name "Net-(IC2-VREF-AC2)") (class "Default")
      (node (ref "C21") (pin "2") (pinfunction "2_2") (pintype "passive"))
      (node (ref "IC2") (pin "26") (pinfunction "VT2_26") (pintype "power_in"))
      (node (ref "IC2") (pin "27") (pinfunction "VREF-AC2_27") (pintype "power_in"))
    )
    (net (code "54") (name "Net-(IC3-OEn)") (class "Default")
      (node (ref "IC3") (pin "2") (pinfunction "OEn_2") (pintype "input"))
      (node (ref "R23") (pin "1") (pinfunction "1_1") (pintype "passive"))
    )
    (net (code "55") (name "Net-(R80-Pad1)") (class "Default")
      (node (ref "R80") (pin "1") (pinfunction "1_1") (pintype "passive"))
      (node (ref "SW1") (pin "4") (pinfunction "4_4") (pintype "bidirectional"))
    )
    (net (code "56") (name "Net-(TR1-P)") (class "Default")
      (node (ref "C3") (pin "2") (pinfunction "2_2") (pintype "passive"))
      (node (ref "R1") (pin "1") (pinfunction "1_1") (pintype "passive"))
      (node (ref "TR1") (pin "4") (pinfunction "P_4") (pintype "passive"))
    )
    (net (code "57") (name "P3V3") (class "Default")
      (node (ref "C31") (pin "2") (pinfunction "2_2") (pintype "passive"))
      (node (ref "C39") (pin "2") (pinfunction "2_2") (pintype "passive"))
      (node (ref "C8") (pin "1") (pinfunction "1_1") (pintype "passive"))
      (node (ref "IC3") (pin "1") (pinfunction "RSVD1_1") (pintype "power_in"))
      (node (ref "IC3") (pin "10") (pinfunction "RSVD2_10") (pintype "power_in"))
      (node (ref "IC3") (pin "6") (pinfunction "VDD_6") (pintype "power_in"))
      (node (ref "L1") (pin "1") (pinfunction "1_1") (pintype "passive"))
      (node (ref "L2") (pin "2") (pinfunction "2_2") (pintype "passive"))
      (node (ref "OSC1") (pin "6") (pinfunction "VCC_6") (pintype "power_in"))
      (node (ref "R22") (pin "2") (pinfunction "2_2") (pintype "passive"))
      (node (ref "R256") (pin "2") (pinfunction "2_2") (pintype "passive"))
    )
    (net (code "58") (name "P3V3_ADCLK") (class "Default")
      (node (ref "C32") (pin "2") (pinfunction "2_2") (pintype "passive"))
      (node (ref "C33") (pin "2") (pinfunction "2_2") (pintype "passive"))
      (node (ref "C34") (pin "2") (pinfunction "2_2") (pintype "passive"))
      (node (ref "C35") (pin "2") (pinfunction "2_2") (pintype "passive"))
      (node (ref "C36") (pin "2") (pinfunction "2_2") (pintype "passive"))
      (node (ref "C37") (pin "2") (pinfunction "2_2") (pintype "passive"))
      (node (ref "C38") (pin "2") (pinfunction "2_2") (pintype "passive"))
      (node (ref "IC1") (pin "10") (pinfunction "VCC_10") (pintype "power_in"))
      (node (ref "IC1") (pin "15") (pinfunction "VCC_15") (pintype "power_in"))
      (node (ref "IC1") (pin "16") (pinfunction "VCC_16") (pintype "power_in"))
      (node (ref "IC1") (pin "25") (pinfunction "VCC_25") (pintype "power_in"))
      (node (ref "IC1") (pin "26") (pinfunction "VCC_26") (pintype "power_in"))
      (node (ref "IC1") (pin "31") (pinfunction "VCC_31") (pintype "power_in"))
      (node (ref "L2") (pin "1") (pinfunction "1_1") (pintype "passive"))
    )
    (net (code "59") (name "P3V3_CLK_MUX") (class "Default")
      (node (ref "C10") (pin "1") (pinfunction "1_1") (pintype "passive"))
      (node (ref "C16") (pin "1") (pinfunction "1_1") (pintype "passive"))
      (node (ref "C21") (pin "1") (pinfunction "1_1") (pintype "passive"))
      (node (ref "C22") (pin "2") (pinfunction "2_2") (pintype "passive"))
      (node (ref "C23") (pin "2") (pinfunction "2_2") (pintype "passive"))
      (node (ref "C24") (pin "2") (pinfunction "2_2") (pintype "passive"))
      (node (ref "C25") (pin "2") (pinfunction "2_2") (pintype "passive"))
      (node (ref "C26") (pin "2") (pinfunction "2_2") (pintype "passive"))
      (node (ref "C27") (pin "2") (pinfunction "2_2") (pintype "passive"))
      (node (ref "C28") (pin "2") (pinfunction "2_2") (pintype "passive"))
      (node (ref "IC2") (pin "10") (pinfunction "VCC_10") (pintype "power_in"))
      (node (ref "IC2") (pin "13") (pinfunction "VCC_13") (pintype "power_in"))
      (node (ref "IC2") (pin "16") (pinfunction "VCC_16") (pintype "power_in"))
      (node (ref "IC2") (pin "17") (pinfunction "VCC_17") (pintype "power_in"))
      (node (ref "IC2") (pin "20") (pinfunction "VCC_20") (pintype "power_in"))
      (node (ref "IC2") (pin "23") (pinfunction "VCC_23") (pintype "power_in"))
      (node (ref "L1") (pin "2") (pinfunction "2_2") (pintype "passive"))
    )
    (net (code "60") (name "unconnected-(IC1-NC-Pad9)") (class "Default")
      (node (ref "IC1") (pin "9") (pinfunction "NC_9") (pintype "passive+no_connect"))
    )
    (net (code "61") (name "unconnected-(IC1-Q3-Pad22)") (class "Default")
      (node (ref "IC1") (pin "22") (pinfunction "Q3_22") (pintype "output+no_connect"))
    )
    (net (code "62") (name "unconnected-(IC1-Q4-Pad20)") (class "Default")
      (node (ref "IC1") (pin "20") (pinfunction "Q4_20") (pintype "output+no_connect"))
    )
    (net (code "63") (name "unconnected-(IC1-Q5-Pad18)") (class "Default")
      (node (ref "IC1") (pin "18") (pinfunction "Q5_18") (pintype "output+no_connect"))
    )
    (net (code "64") (name "unconnected-(IC1-Q6-Pad14)") (class "Default")
      (node (ref "IC1") (pin "14") (pinfunction "Q6_14") (pintype "output+no_connect"))
    )
    (net (code "65") (name "unconnected-(IC1-Q7-Pad12)") (class "Default")
      (node (ref "IC1") (pin "12") (pinfunction "Q7_12") (pintype "output+no_connect"))
    )
    (net (code "66") (name "unconnected-(IC1-~{Q3}-Pad21)") (class "Default")
      (node (ref "IC1") (pin "21") (pinfunction "~{Q3}_21") (pintype "output+no_connect"))
    )
    (net (code "67") (name "unconnected-(IC1-~{Q4}-Pad19)") (class "Default")
      (node (ref "IC1") (pin "19") (pinfunction "~{Q4}_19") (pintype "output+no_connect"))
    )
    (net (code "68") (name "unconnected-(IC1-~{Q5}-Pad17)") (class "Default")
      (node (ref "IC1") (pin "17") (pinfunction "~{Q5}_17") (pintype "output+no_connect"))
    )
    (net (code "69") (name "unconnected-(IC1-~{Q6}-Pad13)") (class "Default")
      (node (ref "IC1") (pin "13") (pinfunction "~{Q6}_13") (pintype "output+no_connect"))
    )
    (net (code "70") (name "unconnected-(IC1-~{Q7}-Pad11)") (class "Default")
      (node (ref "IC1") (pin "11") (pinfunction "~{Q7}_11") (pintype "output+no_connect"))
    )
    (net (code "71") (name "unconnected-(IC2-IN0-Pad1)") (class "Default")
      (node (ref "IC2") (pin "1") (pinfunction "IN0_1") (pintype "input+no_connect"))
    )
    (net (code "72") (name "unconnected-(IC2-NC-Pad14)") (class "Default")
      (node (ref "IC2") (pin "14") (pinfunction "NC_14") (pintype "passive+no_connect"))
    )
    (net (code "73") (name "unconnected-(IC2-NC-Pad19)") (class "Default")
      (node (ref "IC2") (pin "19") (pinfunction "NC_19") (pintype "passive+no_connect"))
    )
    (net (code "74") (name "unconnected-(IC2-Q1-Pad22)") (class "Default")
      (node (ref "IC2") (pin "22") (pinfunction "Q1_22") (pintype "output+no_connect"))
    )
    (net (code "75") (name "unconnected-(IC2-VREF-AC3-Pad31)") (class "Default")
      (node (ref "IC2") (pin "31") (pinfunction "VREF-AC3_31") (pintype "power_in+no_connect"))
    )
    (net (code "76") (name "unconnected-(IC2-VT1-Pad6)") (class "Default")
      (node (ref "IC2") (pin "6") (pinfunction "VT1_6") (pintype "power_in+no_connect"))
    )
    (net (code "77") (name "unconnected-(IC2-VT3-Pad30)") (class "Default")
      (node (ref "IC2") (pin "30") (pinfunction "VT3_30") (pintype "power_in+no_connect"))
    )
    (net (code "78") (name "unconnected-(IC2-~{IN}0-Pad4)") (class "Default")
      (node (ref "IC2") (pin "4") (pinfunction "~{IN}0_4") (pintype "input+no_connect"))
    )
    (net (code "79") (name "unconnected-(IC2-~{Q}1-Pad21)") (class "Default")
      (node (ref "IC2") (pin "21") (pinfunction "~{Q}1_21") (pintype "output+no_connect"))
    )
    (net (code "80") (name "unconnected-(IC3-C0+-Pad15)") (class "Default")
      (node (ref "IC3") (pin "15") (pinfunction "C0+_15") (pintype "bidirectional+no_connect"))
    )
    (net (code "81") (name "unconnected-(IC3-C0--Pad14)") (class "Default")
      (node (ref "IC3") (pin "14") (pinfunction "C0-_14") (pintype "bidirectional+no_connect"))
    )
    (net (code "82") (name "unconnected-(OSC1-NC-Pad2)") (class "Default")
      (node (ref "OSC1") (pin "2") (pinfunction "NC_2") (pintype "input+no_connect"))
    )
    (net (code "83") (name "unconnected-(TR1-NC-Pad2)") (class "Default")
      (node (ref "TR1") (pin "2") (pinfunction "NC_2") (pintype "passive+no_connect"))
    )
  )
)
